# BB_Power_Supply.net
KiCad netlist of a schematic drawn in EAGLE
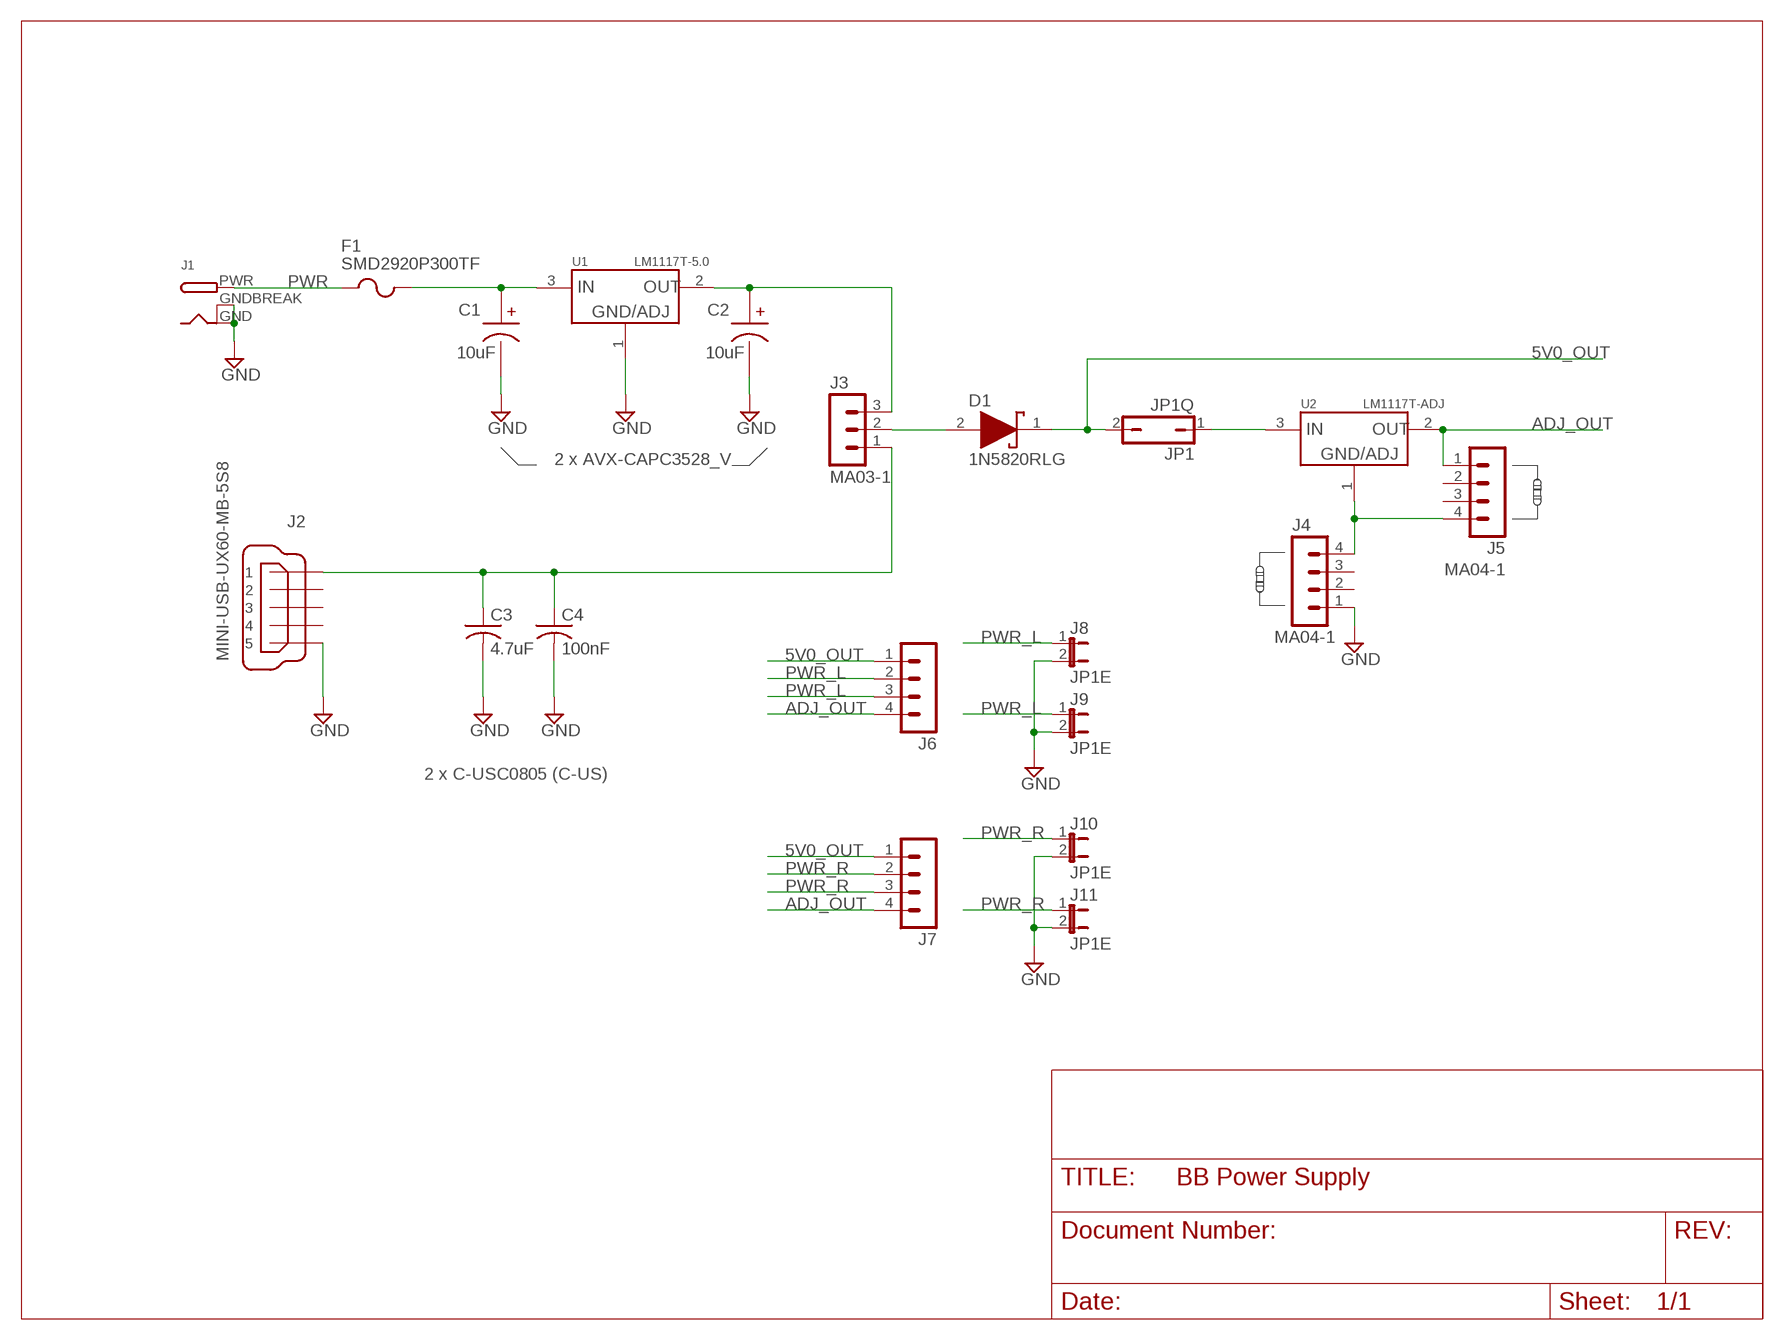
[diagram p0: schematic, sheet 1]

(export (version "E")
  (design (tool "Eeschema 10.0.6"))
  (components
    (comp (ref "C1")
      (value "10uF")
      (footprint "eagle-import:AVX-CAPC3528_V")
      (libsource (lib "eagle-import") (part "TAJB106K020R"))
    )
    (comp (ref "C2")
      (value "10uF")
      (footprint "eagle-import:AVX-CAPC3528_V")
      (libsource (lib "eagle-import") (part "TAJB106K020R"))
    )
    (comp (ref "C3")
      (value "4.7uF")
      (footprint "eagle-import:C0805")
      (libsource (lib "eagle-import") (part "C-USC0805"))
    )
    (comp (ref "C4")
      (value "100nF")
      (footprint "eagle-import:C0805")
      (libsource (lib "eagle-import") (part "C-USC0805"))
    )
    (comp (ref "D1")
      (value "1N5820RLG")
      (footprint "eagle-import:ONSC-AXIAL_LEAD-2-267-05_V")
      (libsource (lib "eagle-import") (part "1N5820RLG"))
    )
    (comp (ref "F1")
      (value "SMD2920P300TF")
      (footprint "eagle-import:FUSE2920")
      (libsource (lib "eagle-import") (part "SMD2920P300TF"))
    )
    (comp (ref "J1")
      (value "DCBARRELPTH")
      (footprint "eagle-import:DCJACK_2MM_PTH")
      (libsource (lib "eagle-import") (part "DCBARRELPTH"))
    )
    (comp (ref "J2")
      (value "MINI-USB-UX60-MB-5S8")
      (footprint "eagle-import:UX60-MB-5S8")
      (libsource (lib "eagle-import") (part "MINI-USB-UX60-MB-5S8"))
    )
    (comp (ref "J3")
      (value "MA03-1")
      (footprint "eagle-import:MA03-1")
      (libsource (lib "eagle-import") (part "MA03-1"))
    )
    (comp (ref "J4")
      (value "MA04-1")
      (footprint "eagle-import:MA04-1")
      (libsource (lib "eagle-import") (part "MA04-1"))
    )
    (comp (ref "J5")
      (value "MA04-1")
      (footprint "eagle-import:MA04-1")
      (libsource (lib "eagle-import") (part "MA04-1"))
    )
    (comp (ref "J6")
      (value "MA04-1")
      (footprint "eagle-import:MA04-1")
      (libsource (lib "eagle-import") (part "MA04-1"))
    )
    (comp (ref "J7")
      (value "MA04-1")
      (footprint "eagle-import:MA04-1")
      (libsource (lib "eagle-import") (part "MA04-1"))
    )
    (comp (ref "J8")
      (value "JP1E")
      (footprint "eagle-import:JP1")
      (libsource (lib "eagle-import") (part "JP1E"))
    )
    (comp (ref "J9")
      (value "JP1E")
      (footprint "eagle-import:JP1")
      (libsource (lib "eagle-import") (part "JP1E"))
    )
    (comp (ref "J10")
      (value "JP1E")
      (footprint "eagle-import:JP1")
      (libsource (lib "eagle-import") (part "JP1E"))
    )
    (comp (ref "J11")
      (value "JP1E")
      (footprint "eagle-import:JP1")
      (libsource (lib "eagle-import") (part "JP1E"))
    )
    (comp (ref "JP1")
      (value "JP1Q")
      (footprint "eagle-import:JP1")
      (libsource (lib "eagle-import") (part "JP1Q"))
    )
    (comp (ref "U1")
      (value "LM1117T-5.0")
      (footprint "eagle-import:TO-220")
      (libsource (lib "eagle-import") (part "LM1117T-5.0"))
    )
    (comp (ref "U2")
      (value "LM1117T-ADJ")
      (footprint "eagle-import:TO-220")
      (libsource (lib "eagle-import") (part "LM1117T-ADJ"))
    )
  )
  (nets
    (net (code "1") (name "/5V0_OUT") (class "Default")
      (node (ref "D1") (pin "1") (pinfunction "K_1") (pintype "bidirectional"))
      (node (ref "J6") (pin "1") (pinfunction "1_1") (pintype "passive"))
      (node (ref "J7") (pin "1") (pinfunction "1_1") (pintype "passive"))
      (node (ref "JP1") (pin "2") (pinfunction "2_2") (pintype "passive"))
    )
    (net (code "2") (name "/ADJ_OUT") (class "Default")
      (node (ref "J5") (pin "1") (pinfunction "1_1") (pintype "passive"))
      (node (ref "J6") (pin "4") (pinfunction "4_4") (pintype "passive"))
      (node (ref "J7") (pin "4") (pinfunction "4_4") (pintype "passive"))
      (node (ref "U2") (pin "2") (pinfunction "OUT_2") (pintype "bidirectional"))
    )
    (net (code "3") (name "/PWR") (class "Default")
      (node (ref "F1") (pin "1") (pinfunction "1_1") (pintype "bidirectional"))
      (node (ref "J1") (pin "PWR") (pinfunction "PWR_PWR") (pintype "power_in"))
    )
    (net (code "4") (name "/PWR_L") (class "Default")
      (node (ref "J6") (pin "2") (pinfunction "2_2") (pintype "passive"))
      (node (ref "J6") (pin "3") (pinfunction "3_3") (pintype "passive"))
      (node (ref "J8") (pin "1") (pinfunction "1_1") (pintype "passive"))
      (node (ref "J9") (pin "1") (pinfunction "1_1") (pintype "passive"))
    )
    (net (code "5") (name "/PWR_R") (class "Default")
      (node (ref "J10") (pin "1") (pinfunction "1_1") (pintype "passive"))
      (node (ref "J11") (pin "1") (pinfunction "1_1") (pintype "passive"))
      (node (ref "J7") (pin "2") (pinfunction "2_2") (pintype "passive"))
      (node (ref "J7") (pin "3") (pinfunction "3_3") (pintype "passive"))
    )
    (net (code "6") (name "GND") (class "Default")
      (node (ref "C1") (pin "2") (pinfunction "2_2") (pintype "bidirectional"))
      (node (ref "C2") (pin "2") (pinfunction "2_2") (pintype "bidirectional"))
      (node (ref "C3") (pin "2") (pinfunction "2_2") (pintype "passive"))
      (node (ref "C4") (pin "2") (pinfunction "2_2") (pintype "passive"))
      (node (ref "J1") (pin "GND") (pinfunction "GND_GND") (pintype "power_in"))
      (node (ref "J1") (pin "GNDBREAK") (pinfunction "GNDBREAK_GNDBREAK") (pintype "power_in"))
      (node (ref "J10") (pin "2") (pinfunction "2_2") (pintype "passive"))
      (node (ref "J11") (pin "2") (pinfunction "2_2") (pintype "passive"))
      (node (ref "J2") (pin "5") (pinfunction "5_5") (pintype "input"))
      (node (ref "J4") (pin "1") (pinfunction "1_1") (pintype "passive"))
      (node (ref "J8") (pin "2") (pinfunction "2_2") (pintype "passive"))
      (node (ref "J9") (pin "2") (pinfunction "2_2") (pintype "passive"))
      (node (ref "U1") (pin "1") (pinfunction "GND_1") (pintype "bidirectional"))
    )
    (net (code "7") (name "Net-(C3-Pad1)") (class "Default")
      (node (ref "C3") (pin "1") (pinfunction "1_1") (pintype "passive"))
      (node (ref "C4") (pin "1") (pinfunction "1_1") (pintype "passive"))
      (node (ref "J2") (pin "1") (pinfunction "1_1") (pintype "input"))
      (node (ref "J3") (pin "1") (pinfunction "1_1") (pintype "passive"))
    )
    (net (code "8") (name "Net-(D1-A)") (class "Default")
      (node (ref "D1") (pin "2") (pinfunction "A_2") (pintype "bidirectional"))
      (node (ref "J3") (pin "2") (pinfunction "2_2") (pintype "passive"))
    )
    (net (code "9") (name "Net-(U1-IN)") (class "Default")
      (node (ref "C1") (pin "1") (pinfunction "1_1") (pintype "bidirectional"))
      (node (ref "F1") (pin "2") (pinfunction "2_2") (pintype "bidirectional"))
      (node (ref "U1") (pin "3") (pinfunction "IN_3") (pintype "bidirectional"))
    )
    (net (code "10") (name "Net-(U1-OUT)") (class "Default")
      (node (ref "C2") (pin "1") (pinfunction "1_1") (pintype "bidirectional"))
      (node (ref "J3") (pin "3") (pinfunction "3_3") (pintype "passive"))
      (node (ref "U1") (pin "2") (pinfunction "OUT_2") (pintype "bidirectional"))
    )
    (net (code "11") (name "Net-(U2-GND)") (class "Default")
      (node (ref "J4") (pin "4") (pinfunction "4_4") (pintype "passive"))
      (node (ref "J5") (pin "4") (pinfunction "4_4") (pintype "passive"))
      (node (ref "U2") (pin "1") (pinfunction "GND_1") (pintype "bidirectional"))
    )
    (net (code "12") (name "Net-(U2-IN)") (class "Default")
      (node (ref "JP1") (pin "1") (pinfunction "1_1") (pintype "passive"))
      (node (ref "U2") (pin "3") (pinfunction "IN_3") (pintype "bidirectional"))
    )
    (net (code "13") (name "unconnected-(J2-Pad2)") (class "Default")
      (node (ref "J2") (pin "2") (pinfunction "2_2") (pintype "input"))
    )
    (net (code "14") (name "unconnected-(J2-Pad3)") (class "Default")
      (node (ref "J2") (pin "3") (pinfunction "3_3") (pintype "input"))
    )
    (net (code "15") (name "unconnected-(J2-Pad4)") (class "Default")
      (node (ref "J2") (pin "4") (pinfunction "4_4") (pintype "input"))
    )
    (net (code "16") (name "unconnected-(J4-Pad2)") (class "Default")
      (node (ref "J4") (pin "2") (pinfunction "2_2") (pintype "passive"))
    )
    (net (code "17") (name "unconnected-(J4-Pad3)") (class "Default")
      (node (ref "J4") (pin "3") (pinfunction "3_3") (pintype "passive"))
    )
    (net (code "18") (name "unconnected-(J5-Pad2)") (class "Default")
      (node (ref "J5") (pin "2") (pinfunction "2_2") (pintype "passive"))
    )
    (net (code "19") (name "unconnected-(J5-Pad3)") (class "Default")
      (node (ref "J5") (pin "3") (pinfunction "3_3") (pintype "passive"))
    )
  )
)
